# 6DoF_IMU_MPU6050_Module.net
KiCad netlist of a schematic drawn in EAGLE
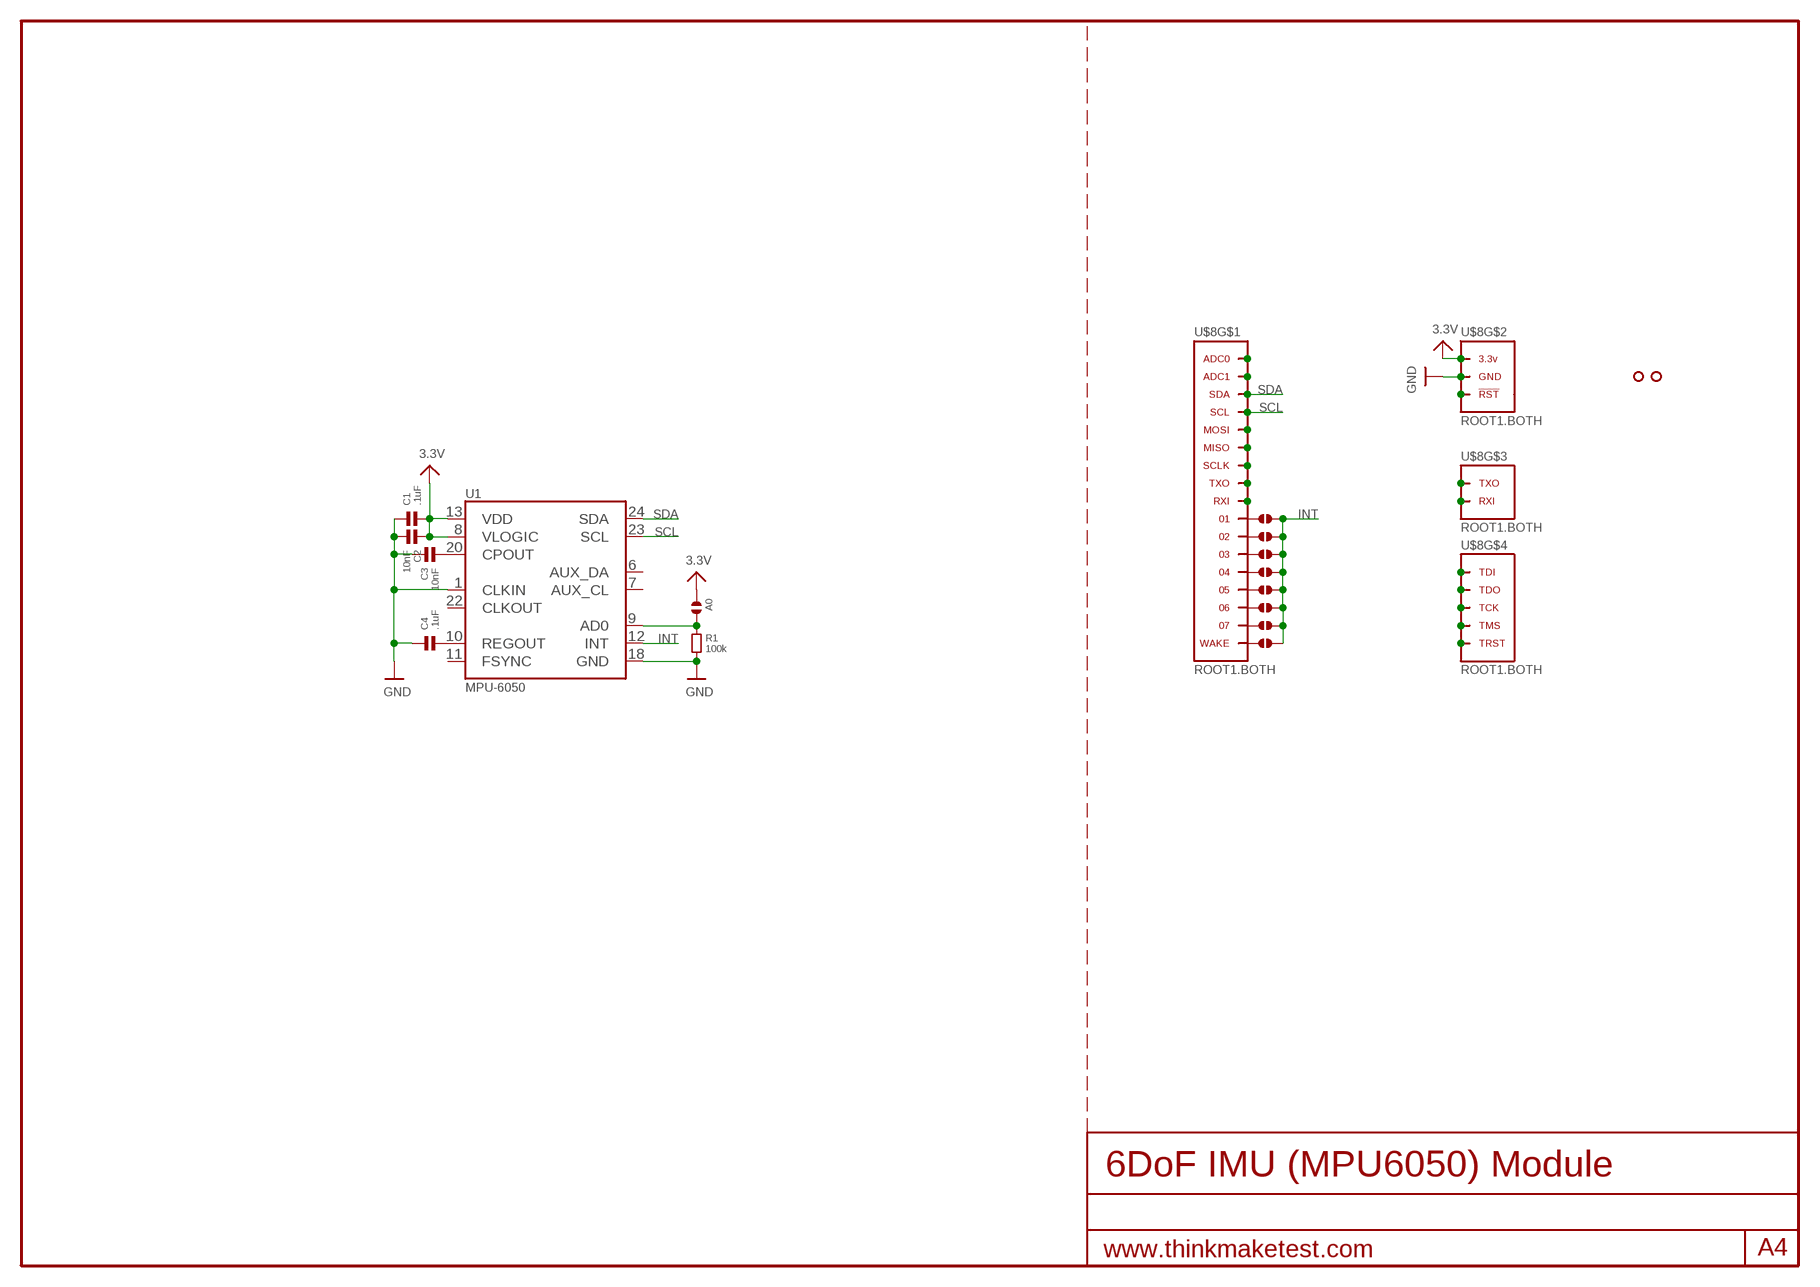
[diagram p0: schematic, sheet 1]

(export (version "E")
  (design (tool "Eeschema 10.0.6"))
  (components
    (comp (ref "A0")
      (value "SOLDERJUMPER.2.LRG")
      (footprint "eagle-import:2.LRG")
      (libsource (lib "eagle-import") (part "SOLDERJUMPER.2.LRG"))
    )
    (comp (ref "C1")
      (value ".1uF")
      (footprint "eagle-import:0603")
      (libsource (lib "eagle-import") (part "CAPACITOR.0603"))
    )
    (comp (ref "C2")
      (value "10nF")
      (footprint "eagle-import:0603")
      (libsource (lib "eagle-import") (part "CAPACITOR.0603"))
    )
    (comp (ref "C3")
      (value "10nF")
      (footprint "eagle-import:0603")
      (libsource (lib "eagle-import") (part "CAPACITOR.0603"))
    )
    (comp (ref "C4")
      (value ".1uF")
      (footprint "eagle-import:0603")
      (libsource (lib "eagle-import") (part "CAPACITOR.0603"))
    )
    (comp (ref "J1")
      (value "SOLDERJUMPER.2.SML")
      (footprint "eagle-import:2.SML")
      (libsource (lib "eagle-import") (part "SOLDERJUMPER.2.SML"))
    )
    (comp (ref "J2")
      (value "SOLDERJUMPER.2.SML")
      (footprint "eagle-import:2.SML")
      (libsource (lib "eagle-import") (part "SOLDERJUMPER.2.SML"))
    )
    (comp (ref "J3")
      (value "SOLDERJUMPER.2.SML")
      (footprint "eagle-import:2.SML")
      (libsource (lib "eagle-import") (part "SOLDERJUMPER.2.SML"))
    )
    (comp (ref "J4")
      (value "SOLDERJUMPER.2.SML")
      (footprint "eagle-import:2.SML")
      (libsource (lib "eagle-import") (part "SOLDERJUMPER.2.SML"))
    )
    (comp (ref "J5")
      (value "SOLDERJUMPER.2.SML")
      (footprint "eagle-import:2.SML")
      (libsource (lib "eagle-import") (part "SOLDERJUMPER.2.SML"))
    )
    (comp (ref "J6")
      (value "SOLDERJUMPER.2.SML")
      (footprint "eagle-import:2.SML")
      (libsource (lib "eagle-import") (part "SOLDERJUMPER.2.SML"))
    )
    (comp (ref "J7")
      (value "SOLDERJUMPER.2.SML")
      (footprint "eagle-import:2.SML")
      (libsource (lib "eagle-import") (part "SOLDERJUMPER.2.SML"))
    )
    (comp (ref "J8")
      (value "SOLDERJUMPER.2.SML")
      (footprint "eagle-import:2.SML")
      (libsource (lib "eagle-import") (part "SOLDERJUMPER.2.SML"))
    )
    (comp (ref "R1")
      (value "100k")
      (footprint "eagle-import:0603")
      (libsource (lib "eagle-import") (part "RESISTOR.0603"))
    )
    (comp (ref "U$3")
      (value "HOLE.2MM")
      (footprint "eagle-import:2MM")
      (libsource (lib "eagle-import") (part "HOLE.2MM"))
    )
    (comp (ref "U$4")
      (value "HOLE.2MM")
      (footprint "eagle-import:2MM")
      (libsource (lib "eagle-import") (part "HOLE.2MM"))
    )
    (comp (ref "U$8")
      (value "ROOT1.BOTH")
      (footprint "eagle-import:ROOT1.BOTH")
      (libsource (lib "eagle-import") (part "ROOT1.BOTH"))
    )
    (comp (ref "U1")
      (value "MPU-6050")
      (footprint "eagle-import:QFN")
      (libsource (lib "eagle-import") (part "MPU-6050"))
    )
  )
  (nets
    (net (code "1") (name "/INT") (class "Default")
      (node (ref "J1") (pin "2") (pinfunction "2_2") (pintype "bidirectional"))
      (node (ref "J2") (pin "2") (pinfunction "2_2") (pintype "bidirectional"))
      (node (ref "J3") (pin "2") (pinfunction "2_2") (pintype "bidirectional"))
      (node (ref "J4") (pin "2") (pinfunction "2_2") (pintype "bidirectional"))
      (node (ref "J5") (pin "2") (pinfunction "2_2") (pintype "bidirectional"))
      (node (ref "J6") (pin "2") (pinfunction "2_2") (pintype "bidirectional"))
      (node (ref "J7") (pin "2") (pinfunction "2_2") (pintype "bidirectional"))
      (node (ref "J8") (pin "2") (pinfunction "2_2") (pintype "bidirectional"))
      (node (ref "U1") (pin "12") (pinfunction "INT_12") (pintype "bidirectional"))
    )
    (net (code "2") (name "/SCL") (class "Default")
      (node (ref "U$8") (pin "SCL") (pinfunction "SCL_SCL") (pintype "bidirectional"))
      (node (ref "U$8") (pin "SCL@1") (pinfunction "SCL_SCL@1") (pintype "bidirectional"))
      (node (ref "U$8") (pin "SCL@VIA") (pinfunction "SCL_SCL@VIA") (pintype "bidirectional"))
      (node (ref "U1") (pin "23") (pinfunction "SCL_23") (pintype "bidirectional"))
    )
    (net (code "3") (name "/SDA") (class "Default")
      (node (ref "U$8") (pin "SDA") (pinfunction "SDA_SDA") (pintype "bidirectional"))
      (node (ref "U$8") (pin "SDA@1") (pinfunction "SDA_SDA@1") (pintype "bidirectional"))
      (node (ref "U$8") (pin "SDA@VIA") (pinfunction "SDA_SDA@VIA") (pintype "bidirectional"))
      (node (ref "U1") (pin "24") (pinfunction "SDA_24") (pintype "bidirectional"))
    )
    (net (code "4") (name "3.3V") (class "Default")
      (node (ref "A0") (pin "1") (pinfunction "1_1") (pintype "bidirectional"))
      (node (ref "C1") (pin "2") (pinfunction "2_2") (pintype "bidirectional"))
      (node (ref "C2") (pin "1") (pinfunction "1_1") (pintype "bidirectional"))
      (node (ref "U$8") (pin "3.3V@1") (pinfunction "3.3V_3.3V@1") (pintype "bidirectional"))
      (node (ref "U$8") (pin "3.3V@10") (pinfunction "3.3V_3.3V@10") (pintype "bidirectional"))
      (node (ref "U$8") (pin "3.3V@11") (pinfunction "3.3V_3.3V@11") (pintype "bidirectional"))
      (node (ref "U$8") (pin "3.3V@12") (pinfunction "3.3V_3.3V@12") (pintype "bidirectional"))
      (node (ref "U$8") (pin "3.3V@13") (pinfunction "3.3V_3.3V@13") (pintype "bidirectional"))
      (node (ref "U$8") (pin "3.3V@14") (pinfunction "3.3V_3.3V@14") (pintype "bidirectional"))
      (node (ref "U$8") (pin "3.3V@15") (pinfunction "3.3V_3.3V@15") (pintype "bidirectional"))
      (node (ref "U$8") (pin "3.3V@16") (pinfunction "3.3V_3.3V@16") (pintype "bidirectional"))
      (node (ref "U$8") (pin "3.3V@17") (pinfunction "3.3V_3.3V@17") (pintype "bidirectional"))
      (node (ref "U$8") (pin "3.3V@18") (pinfunction "3.3V_3.3V@18") (pintype "bidirectional"))
      (node (ref "U$8") (pin "3.3V@19") (pinfunction "3.3V_3.3V@19") (pintype "bidirectional"))
      (node (ref "U$8") (pin "3.3V@2") (pinfunction "3.3V_3.3V@2") (pintype "bidirectional"))
      (node (ref "U$8") (pin "3.3V@20") (pinfunction "3.3V_3.3V@20") (pintype "bidirectional"))
      (node (ref "U$8") (pin "3.3V@21") (pinfunction "3.3V_3.3V@21") (pintype "bidirectional"))
      (node (ref "U$8") (pin "3.3V@22") (pinfunction "3.3V_3.3V@22") (pintype "bidirectional"))
      (node (ref "U$8") (pin "3.3V@23") (pinfunction "3.3V_3.3V@23") (pintype "bidirectional"))
      (node (ref "U$8") (pin "3.3V@24") (pinfunction "3.3V_3.3V@24") (pintype "bidirectional"))
      (node (ref "U$8") (pin "3.3V@3") (pinfunction "3.3V_3.3V@3") (pintype "bidirectional"))
      (node (ref "U$8") (pin "3.3V@4") (pinfunction "3.3V_3.3V@4") (pintype "bidirectional"))
      (node (ref "U$8") (pin "3.3V@5") (pinfunction "3.3V_3.3V@5") (pintype "bidirectional"))
      (node (ref "U$8") (pin "3.3V@6") (pinfunction "3.3V_3.3V@6") (pintype "bidirectional"))
      (node (ref "U$8") (pin "3.3V@7") (pinfunction "3.3V_3.3V@7") (pintype "bidirectional"))
      (node (ref "U$8") (pin "3.3V@8") (pinfunction "3.3V_3.3V@8") (pintype "bidirectional"))
      (node (ref "U$8") (pin "3.3V@9") (pinfunction "3.3V_3.3V@9") (pintype "bidirectional"))
      (node (ref "U$8") (pin "3.3V@VIA") (pinfunction "3.3V_3.3V@VIA") (pintype "bidirectional"))
      (node (ref "U1") (pin "13") (pinfunction "VDD_13") (pintype "bidirectional"))
      (node (ref "U1") (pin "8") (pinfunction "VLOGIC_8") (pintype "bidirectional"))
    )
    (net (code "5") (name "GND") (class "Default")
      (node (ref "C1") (pin "1") (pinfunction "1_1") (pintype "bidirectional"))
      (node (ref "C2") (pin "2") (pinfunction "2_2") (pintype "bidirectional"))
      (node (ref "C3") (pin "1") (pinfunction "1_1") (pintype "bidirectional"))
      (node (ref "C4") (pin "1") (pinfunction "1_1") (pintype "bidirectional"))
      (node (ref "R1") (pin "2") (pinfunction "2_2") (pintype "bidirectional"))
      (node (ref "U$8") (pin "GND@1") (pinfunction "GND_GND@1") (pintype "bidirectional"))
      (node (ref "U$8") (pin "GND@10") (pinfunction "GND_GND@10") (pintype "bidirectional"))
      (node (ref "U$8") (pin "GND@11") (pinfunction "GND_GND@11") (pintype "bidirectional"))
      (node (ref "U$8") (pin "GND@12") (pinfunction "GND_GND@12") (pintype "bidirectional"))
      (node (ref "U$8") (pin "GND@13") (pinfunction "GND_GND@13") (pintype "bidirectional"))
      (node (ref "U$8") (pin "GND@14") (pinfunction "GND_GND@14") (pintype "bidirectional"))
      (node (ref "U$8") (pin "GND@15") (pinfunction "GND_GND@15") (pintype "bidirectional"))
      (node (ref "U$8") (pin "GND@16") (pinfunction "GND_GND@16") (pintype "bidirectional"))
      (node (ref "U$8") (pin "GND@17") (pinfunction "GND_GND@17") (pintype "bidirectional"))
      (node (ref "U$8") (pin "GND@18") (pinfunction "GND_GND@18") (pintype "bidirectional"))
      (node (ref "U$8") (pin "GND@19") (pinfunction "GND_GND@19") (pintype "bidirectional"))
      (node (ref "U$8") (pin "GND@2") (pinfunction "GND_GND@2") (pintype "bidirectional"))
      (node (ref "U$8") (pin "GND@20") (pinfunction "GND_GND@20") (pintype "bidirectional"))
      (node (ref "U$8") (pin "GND@21") (pinfunction "GND_GND@21") (pintype "bidirectional"))
      (node (ref "U$8") (pin "GND@22") (pinfunction "GND_GND@22") (pintype "bidirectional"))
      (node (ref "U$8") (pin "GND@23") (pinfunction "GND_GND@23") (pintype "bidirectional"))
      (node (ref "U$8") (pin "GND@24") (pinfunction "GND_GND@24") (pintype "bidirectional"))
      (node (ref "U$8") (pin "GND@25") (pinfunction "GND_GND@25") (pintype "bidirectional"))
      (node (ref "U$8") (pin "GND@26") (pinfunction "GND_GND@26") (pintype "bidirectional"))
      (node (ref "U$8") (pin "GND@3") (pinfunction "GND_GND@3") (pintype "bidirectional"))
      (node (ref "U$8") (pin "GND@4") (pinfunction "GND_GND@4") (pintype "bidirectional"))
      (node (ref "U$8") (pin "GND@5") (pinfunction "GND_GND@5") (pintype "bidirectional"))
      (node (ref "U$8") (pin "GND@6") (pinfunction "GND_GND@6") (pintype "bidirectional"))
      (node (ref "U$8") (pin "GND@7") (pinfunction "GND_GND@7") (pintype "bidirectional"))
      (node (ref "U$8") (pin "GND@8") (pinfunction "GND_GND@8") (pintype "bidirectional"))
      (node (ref "U$8") (pin "GND@9") (pinfunction "GND_GND@9") (pintype "bidirectional"))
      (node (ref "U$8") (pin "GND@VIA") (pinfunction "GND_GND@VIA") (pintype "bidirectional"))
      (node (ref "U1") (pin "1") (pinfunction "CLKIN_1") (pintype "bidirectional"))
      (node (ref "U1") (pin "18") (pinfunction "GND_18") (pintype "bidirectional"))
    )
    (net (code "6") (name "Net-(J1-Pad1)") (class "Default")
      (node (ref "J1") (pin "1") (pinfunction "1_1") (pintype "bidirectional"))
      (node (ref "U$8") (pin "01") (pinfunction "01_01") (pintype "bidirectional"))
      (node (ref "U$8") (pin "01@1") (pinfunction "01_01@1") (pintype "bidirectional"))
      (node (ref "U$8") (pin "01@VIA") (pinfunction "01_01@VIA") (pintype "bidirectional"))
    )
    (net (code "7") (name "Net-(J2-Pad1)") (class "Default")
      (node (ref "J2") (pin "1") (pinfunction "1_1") (pintype "bidirectional"))
      (node (ref "U$8") (pin "02") (pinfunction "02_02") (pintype "bidirectional"))
      (node (ref "U$8") (pin "02@1") (pinfunction "02_02@1") (pintype "bidirectional"))
      (node (ref "U$8") (pin "02@VIA") (pinfunction "02_02@VIA") (pintype "bidirectional"))
    )
    (net (code "8") (name "Net-(J3-Pad1)") (class "Default")
      (node (ref "J3") (pin "1") (pinfunction "1_1") (pintype "bidirectional"))
      (node (ref "U$8") (pin "03") (pinfunction "03_03") (pintype "bidirectional"))
      (node (ref "U$8") (pin "03@1") (pinfunction "03_03@1") (pintype "bidirectional"))
      (node (ref "U$8") (pin "03@VIA") (pinfunction "03_03@VIA") (pintype "bidirectional"))
    )
    (net (code "9") (name "Net-(J4-Pad1)") (class "Default")
      (node (ref "J4") (pin "1") (pinfunction "1_1") (pintype "bidirectional"))
      (node (ref "U$8") (pin "04") (pinfunction "04_04") (pintype "bidirectional"))
      (node (ref "U$8") (pin "04@1") (pinfunction "04_04@1") (pintype "bidirectional"))
      (node (ref "U$8") (pin "04@VIA") (pinfunction "04_04@VIA") (pintype "bidirectional"))
    )
    (net (code "10") (name "Net-(J5-Pad1)") (class "Default")
      (node (ref "J5") (pin "1") (pinfunction "1_1") (pintype "bidirectional"))
      (node (ref "U$8") (pin "05") (pinfunction "05_05") (pintype "bidirectional"))
      (node (ref "U$8") (pin "05@1") (pinfunction "05_05@1") (pintype "bidirectional"))
      (node (ref "U$8") (pin "05@VIA") (pinfunction "05_05@VIA") (pintype "bidirectional"))
    )
    (net (code "11") (name "Net-(J6-Pad1)") (class "Default")
      (node (ref "J6") (pin "1") (pinfunction "1_1") (pintype "bidirectional"))
      (node (ref "U$8") (pin "06") (pinfunction "06_06") (pintype "bidirectional"))
      (node (ref "U$8") (pin "06@1") (pinfunction "06_06@1") (pintype "bidirectional"))
      (node (ref "U$8") (pin "06@VIA") (pinfunction "06_06@VIA") (pintype "bidirectional"))
    )
    (net (code "12") (name "Net-(J7-Pad1)") (class "Default")
      (node (ref "J7") (pin "1") (pinfunction "1_1") (pintype "bidirectional"))
      (node (ref "U$8") (pin "07") (pinfunction "07_07") (pintype "bidirectional"))
      (node (ref "U$8") (pin "07@1") (pinfunction "07_07@1") (pintype "bidirectional"))
      (node (ref "U$8") (pin "07@VIA") (pinfunction "07_07@VIA") (pintype "bidirectional"))
    )
    (net (code "13") (name "Net-(J8-Pad1)") (class "Default")
      (node (ref "J8") (pin "1") (pinfunction "1_1") (pintype "bidirectional"))
      (node (ref "U$8") (pin "WAKE") (pinfunction "WAKE_WAKE") (pintype "bidirectional"))
      (node (ref "U$8") (pin "WAKE@1") (pinfunction "WAKE_WAKE@1") (pintype "bidirectional"))
      (node (ref "U$8") (pin "WAKE@VIA") (pinfunction "WAKE_WAKE@VIA") (pintype "bidirectional"))
    )
    (net (code "14") (name "Net-(U$8-PadADC0)") (class "Default")
      (node (ref "U$8") (pin "ADC0") (pinfunction "ADC0_ADC0") (pintype "bidirectional"))
      (node (ref "U$8") (pin "ADC0@1") (pinfunction "ADC0_ADC0@1") (pintype "bidirectional"))
      (node (ref "U$8") (pin "ADC0@VIA") (pinfunction "ADC0_ADC0@VIA") (pintype "bidirectional"))
    )
    (net (code "15") (name "Net-(U$8-PadADC1)") (class "Default")
      (node (ref "U$8") (pin "ADC1") (pinfunction "ADC1_ADC1") (pintype "bidirectional"))
      (node (ref "U$8") (pin "ADC1@1") (pinfunction "ADC1_ADC1@1") (pintype "bidirectional"))
      (node (ref "U$8") (pin "ADC1@VIA") (pinfunction "ADC1_ADC1@VIA") (pintype "bidirectional"))
    )
    (net (code "16") (name "Net-(U$8-PadMISO)") (class "Default")
      (node (ref "U$8") (pin "MISO") (pinfunction "MISO_MISO") (pintype "bidirectional"))
      (node (ref "U$8") (pin "MISO@1") (pinfunction "MISO_MISO@1") (pintype "bidirectional"))
      (node (ref "U$8") (pin "MISO@VIA") (pinfunction "MISO_MISO@VIA") (pintype "bidirectional"))
    )
    (net (code "17") (name "Net-(U$8-PadMOSI)") (class "Default")
      (node (ref "U$8") (pin "MOSI") (pinfunction "MOSI_MOSI") (pintype "bidirectional"))
      (node (ref "U$8") (pin "MOSI@1") (pinfunction "MOSI_MOSI@1") (pintype "bidirectional"))
      (node (ref "U$8") (pin "MOSI@VIA") (pinfunction "MOSI_MOSI@VIA") (pintype "bidirectional"))
    )
    (net (code "18") (name "Net-(U$8-PadRXI)") (class "Default")
      (node (ref "U$8") (pin "RXI") (pinfunction "RXI_RXI") (pintype "bidirectional"))
      (node (ref "U$8") (pin "RXI@1") (pinfunction "RXI_RXI@1") (pintype "bidirectional"))
      (node (ref "U$8") (pin "RXI@VIA") (pinfunction "RXI_RXI@VIA") (pintype "bidirectional"))
    )
    (net (code "19") (name "Net-(U$8-PadSCLK)") (class "Default")
      (node (ref "U$8") (pin "SCLK") (pinfunction "SCLK_SCLK") (pintype "bidirectional"))
      (node (ref "U$8") (pin "SCLK@1") (pinfunction "SCLK_SCLK@1") (pintype "bidirectional"))
      (node (ref "U$8") (pin "SCLK@VIA") (pinfunction "SCLK_SCLK@VIA") (pintype "bidirectional"))
    )
    (net (code "20") (name "Net-(U$8-PadTCK)") (class "Default")
      (node (ref "U$8") (pin "TCK") (pinfunction "TCK_TCK") (pintype "bidirectional"))
      (node (ref "U$8") (pin "TCK@1") (pinfunction "TCK_TCK@1") (pintype "bidirectional"))
      (node (ref "U$8") (pin "TCK@VIA") (pinfunction "TCK_TCK@VIA") (pintype "bidirectional"))
    )
    (net (code "21") (name "Net-(U$8-PadTDI)") (class "Default")
      (node (ref "U$8") (pin "TDI") (pinfunction "TDI_TDI") (pintype "bidirectional"))
      (node (ref "U$8") (pin "TDI@1") (pinfunction "TDI_TDI@1") (pintype "bidirectional"))
      (node (ref "U$8") (pin "TDI@VIA") (pinfunction "TDI_TDI@VIA") (pintype "bidirectional"))
    )
    (net (code "22") (name "Net-(U$8-PadTDO)") (class "Default")
      (node (ref "U$8") (pin "TDO") (pinfunction "TDO_TDO") (pintype "bidirectional"))
      (node (ref "U$8") (pin "TDO@1") (pinfunction "TDO_TDO@1") (pintype "bidirectional"))
      (node (ref "U$8") (pin "TDO@VIA") (pinfunction "TDO_TDO@VIA") (pintype "bidirectional"))
    )
    (net (code "23") (name "Net-(U$8-PadTMS)") (class "Default")
      (node (ref "U$8") (pin "TMS") (pinfunction "TMS_TMS") (pintype "bidirectional"))
      (node (ref "U$8") (pin "TMS@1") (pinfunction "TMS_TMS@1") (pintype "bidirectional"))
      (node (ref "U$8") (pin "TMS@VIA") (pinfunction "TMS_TMS@VIA") (pintype "bidirectional"))
    )
    (net (code "24") (name "Net-(U$8-PadTRST)") (class "Default")
      (node (ref "U$8") (pin "TRST") (pinfunction "TRST_TRST") (pintype "bidirectional"))
      (node (ref "U$8") (pin "TRST@1") (pinfunction "TRST_TRST@1") (pintype "bidirectional"))
      (node (ref "U$8") (pin "TRST@VIA") (pinfunction "TRST_TRST@VIA") (pintype "bidirectional"))
    )
    (net (code "25") (name "Net-(U$8-PadTXO)") (class "Default")
      (node (ref "U$8") (pin "TXO") (pinfunction "TXO_TXO") (pintype "bidirectional"))
      (node (ref "U$8") (pin "TXO@1") (pinfunction "TXO_TXO@1") (pintype "bidirectional"))
      (node (ref "U$8") (pin "TXO@VIA") (pinfunction "TXO_TXO@VIA") (pintype "bidirectional"))
    )
    (net (code "26") (name "Net-(U$8B-~{RST}-PadRST)") (class "Default")
      (node (ref "U$8") (pin "RST") (pinfunction "~{RST}_RST") (pintype "bidirectional"))
      (node (ref "U$8") (pin "RST@1") (pinfunction "~{RST}_RST@1") (pintype "bidirectional"))
      (node (ref "U$8") (pin "RST@VIA") (pinfunction "~{RST}_RST@VIA") (pintype "bidirectional"))
    )
    (net (code "27") (name "Net-(U$8C-RXI-PadRXI.DBG)") (class "Default")
      (node (ref "U$8") (pin "RXI.DBG") (pinfunction "RXI_RXI.DBG") (pintype "bidirectional"))
      (node (ref "U$8") (pin "RXI.DBG@1") (pinfunction "RXI_RXI.DBG@1") (pintype "bidirectional"))
      (node (ref "U$8") (pin "RXI.DBG@VIA") (pinfunction "RXI_RXI.DBG@VIA") (pintype "bidirectional"))
    )
    (net (code "28") (name "Net-(U$8C-TXO-PadTXO.DBG)") (class "Default")
      (node (ref "U$8") (pin "TXO.DBG") (pinfunction "TXO_TXO.DBG") (pintype "bidirectional"))
      (node (ref "U$8") (pin "TXO.DBG@1") (pinfunction "TXO_TXO.DBG@1") (pintype "bidirectional"))
      (node (ref "U$8") (pin "TXO.DBG@VIA") (pinfunction "TXO_TXO.DBG@VIA") (pintype "bidirectional"))
    )
    (net (code "29") (name "Net-(U1-AD0)") (class "Default")
      (node (ref "A0") (pin "2") (pinfunction "2_2") (pintype "bidirectional"))
      (node (ref "R1") (pin "1") (pinfunction "1_1") (pintype "bidirectional"))
      (node (ref "U1") (pin "9") (pinfunction "AD0_9") (pintype "bidirectional"))
    )
    (net (code "30") (name "Net-(U1-CPOUT)") (class "Default")
      (node (ref "C3") (pin "2") (pinfunction "2_2") (pintype "bidirectional"))
      (node (ref "U1") (pin "20") (pinfunction "CPOUT_20") (pintype "bidirectional"))
    )
    (net (code "31") (name "Net-(U1-REGOUT)") (class "Default")
      (node (ref "C4") (pin "2") (pinfunction "2_2") (pintype "bidirectional"))
      (node (ref "U1") (pin "10") (pinfunction "REGOUT_10") (pintype "bidirectional"))
    )
    (net (code "32") (name "unconnected-(U1-AUX_CL-Pad7)") (class "Default")
      (node (ref "U1") (pin "7") (pinfunction "AUX_CL_7") (pintype "bidirectional"))
    )
    (net (code "33") (name "unconnected-(U1-AUX_DA-Pad6)") (class "Default")
      (node (ref "U1") (pin "6") (pinfunction "AUX_DA_6") (pintype "bidirectional"))
    )
    (net (code "34") (name "unconnected-(U1-CLKOUT-Pad22)") (class "Default")
      (node (ref "U1") (pin "22") (pinfunction "CLKOUT_22") (pintype "bidirectional"))
    )
    (net (code "35") (name "unconnected-(U1-FSYNC-Pad11)") (class "Default")
      (node (ref "U1") (pin "11") (pinfunction "FSYNC_11") (pintype "bidirectional"))
    )
  )
)
